# dsp_power.net
KiCad netlist of a schematic drawn in Altium Designer
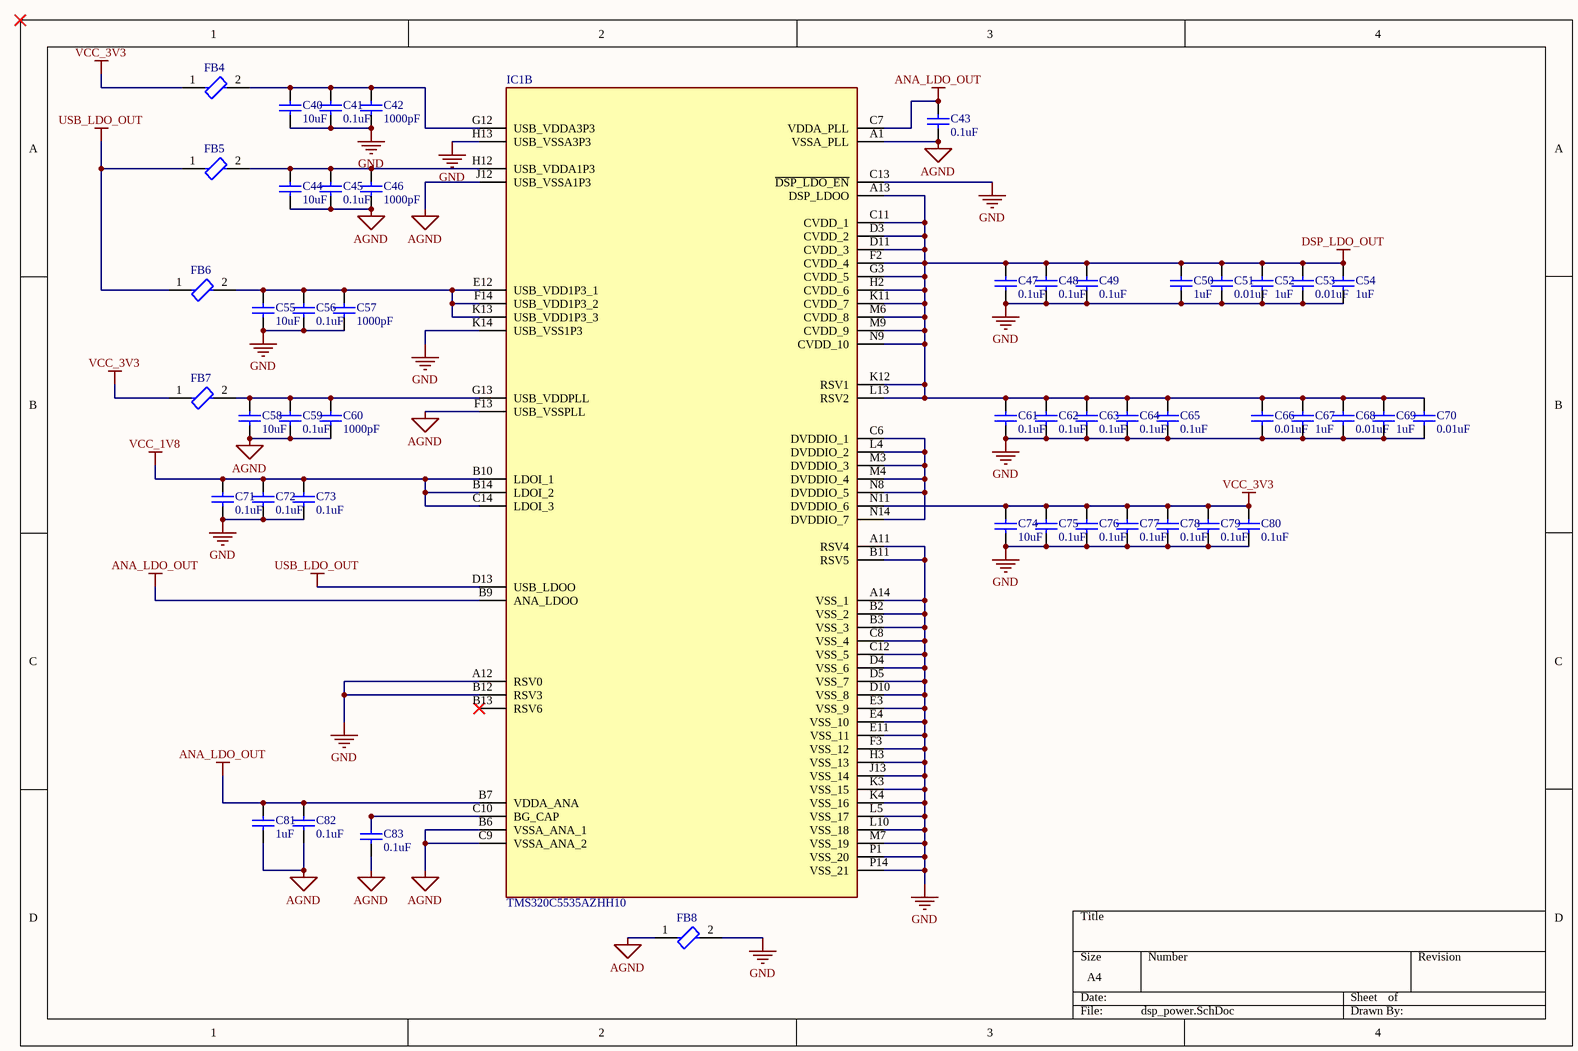
[diagram p0: dsp_power.SchDoc]

(export (version "E")
  (design (tool "Eeschema 10.0.6"))
  (components
    (comp (ref "C40")
      (value "10uF")
      (footprint "0805_C_S")
      (description "Capacitor")
      (fields (field (name "PUBLISHER") "Altium Limited"))
      (libsource (lib "Miscellaneous Devices") (part "Cap"))
    )
    (comp (ref "C41")
      (value "0.1uF")
      (footprint "0805_C_S")
      (description "Capacitor")
      (fields (field (name "PUBLISHER") "Altium Limited"))
      (libsource (lib "Miscellaneous Devices") (part "Cap"))
    )
    (comp (ref "C42")
      (value "1000pF")
      (footprint "0805_C_S")
      (description "Capacitor")
      (fields (field (name "PUBLISHER") "Altium Limited"))
      (libsource (lib "Miscellaneous Devices") (part "Cap"))
    )
    (comp (ref "C43")
      (value "0.1uF")
      (footprint "0805_C_S")
      (description "Capacitor")
      (fields (field (name "PUBLISHER") "Altium Limited"))
      (libsource (lib "Miscellaneous Devices") (part "Cap"))
    )
    (comp (ref "C44")
      (value "10uF")
      (footprint "0805_C_S")
      (description "Capacitor")
      (fields (field (name "PUBLISHER") "Altium Limited"))
      (libsource (lib "Miscellaneous Devices") (part "Cap"))
    )
    (comp (ref "C45")
      (value "0.1uF")
      (footprint "0805_C_S")
      (description "Capacitor")
      (fields (field (name "PUBLISHER") "Altium Limited"))
      (libsource (lib "Miscellaneous Devices") (part "Cap"))
    )
    (comp (ref "C46")
      (value "1000pF")
      (footprint "0805_C_S")
      (description "Capacitor")
      (fields (field (name "PUBLISHER") "Altium Limited"))
      (libsource (lib "Miscellaneous Devices") (part "Cap"))
    )
    (comp (ref "C47")
      (value "0.1uF")
      (footprint "0805_C_S")
      (description "Capacitor")
      (fields (field (name "PUBLISHER") "Altium Limited"))
      (libsource (lib "Miscellaneous Devices") (part "Cap"))
    )
    (comp (ref "C48")
      (value "0.1uF")
      (footprint "0805_C_S")
      (description "Capacitor")
      (fields (field (name "PUBLISHER") "Altium Limited"))
      (libsource (lib "Miscellaneous Devices") (part "Cap"))
    )
    (comp (ref "C49")
      (value "0.1uF")
      (footprint "0805_C_S")
      (description "Capacitor")
      (fields (field (name "PUBLISHER") "Altium Limited"))
      (libsource (lib "Miscellaneous Devices") (part "Cap"))
    )
    (comp (ref "C50")
      (value "1uF")
      (footprint "0805_C_S")
      (description "Capacitor")
      (fields (field (name "PUBLISHER") "Altium Limited"))
      (libsource (lib "Miscellaneous Devices") (part "Cap"))
    )
    (comp (ref "C51")
      (value "0.01uF")
      (footprint "0805_C_S")
      (description "Capacitor")
      (fields (field (name "PUBLISHER") "Altium Limited"))
      (libsource (lib "Miscellaneous Devices") (part "Cap"))
    )
    (comp (ref "C52")
      (value "1uF")
      (footprint "0805_C_S")
      (description "Capacitor")
      (fields (field (name "PUBLISHER") "Altium Limited"))
      (libsource (lib "Miscellaneous Devices") (part "Cap"))
    )
    (comp (ref "C53")
      (value "0.01uF")
      (footprint "0805_C_S")
      (description "Capacitor")
      (fields (field (name "PUBLISHER") "Altium Limited"))
      (libsource (lib "Miscellaneous Devices") (part "Cap"))
    )
    (comp (ref "C54")
      (value "1uF")
      (footprint "0805_C_S")
      (description "Capacitor")
      (fields (field (name "PUBLISHER") "Altium Limited"))
      (libsource (lib "Miscellaneous Devices") (part "Cap"))
    )
    (comp (ref "C55")
      (value "10uF")
      (footprint "0805_C_S")
      (description "Capacitor")
      (fields (field (name "PUBLISHER") "Altium Limited"))
      (libsource (lib "Miscellaneous Devices") (part "Cap"))
    )
    (comp (ref "C56")
      (value "0.1uF")
      (footprint "0805_C_S")
      (description "Capacitor")
      (fields (field (name "PUBLISHER") "Altium Limited"))
      (libsource (lib "Miscellaneous Devices") (part "Cap"))
    )
    (comp (ref "C57")
      (value "1000pF")
      (footprint "0805_C_S")
      (description "Capacitor")
      (fields (field (name "PUBLISHER") "Altium Limited"))
      (libsource (lib "Miscellaneous Devices") (part "Cap"))
    )
    (comp (ref "C58")
      (value "10uF")
      (footprint "0805_C_S")
      (description "Capacitor")
      (fields (field (name "PUBLISHER") "Altium Limited"))
      (libsource (lib "Miscellaneous Devices") (part "Cap"))
    )
    (comp (ref "C59")
      (value "0.1uF")
      (footprint "0805_C_S")
      (description "Capacitor")
      (fields (field (name "PUBLISHER") "Altium Limited"))
      (libsource (lib "Miscellaneous Devices") (part "Cap"))
    )
    (comp (ref "C60")
      (value "1000pF")
      (footprint "0805_C_S")
      (description "Capacitor")
      (fields (field (name "PUBLISHER") "Altium Limited"))
      (libsource (lib "Miscellaneous Devices") (part "Cap"))
    )
    (comp (ref "C61")
      (value "0.1uF")
      (footprint "0805_C_S")
      (description "Capacitor")
      (fields (field (name "PUBLISHER") "Altium Limited"))
      (libsource (lib "Miscellaneous Devices") (part "Cap"))
    )
    (comp (ref "C62")
      (value "0.1uF")
      (footprint "0805_C_S")
      (description "Capacitor")
      (fields (field (name "PUBLISHER") "Altium Limited"))
      (libsource (lib "Miscellaneous Devices") (part "Cap"))
    )
    (comp (ref "C63")
      (value "0.1uF")
      (footprint "0805_C_S")
      (description "Capacitor")
      (fields (field (name "PUBLISHER") "Altium Limited"))
      (libsource (lib "Miscellaneous Devices") (part "Cap"))
    )
    (comp (ref "C64")
      (value "0.1uF")
      (footprint "0805_C_S")
      (description "Capacitor")
      (fields (field (name "PUBLISHER") "Altium Limited"))
      (libsource (lib "Miscellaneous Devices") (part "Cap"))
    )
    (comp (ref "C65")
      (value "0.1uF")
      (footprint "0805_C_S")
      (description "Capacitor")
      (fields (field (name "PUBLISHER") "Altium Limited"))
      (libsource (lib "Miscellaneous Devices") (part "Cap"))
    )
    (comp (ref "C66")
      (value "0.01uF")
      (footprint "0805_C_S")
      (description "Capacitor")
      (fields (field (name "PUBLISHER") "Altium Limited"))
      (libsource (lib "Miscellaneous Devices") (part "Cap"))
    )
    (comp (ref "C67")
      (value "1uF")
      (footprint "0805_C_S")
      (description "Capacitor")
      (fields (field (name "PUBLISHER") "Altium Limited"))
      (libsource (lib "Miscellaneous Devices") (part "Cap"))
    )
    (comp (ref "C68")
      (value "0.01uF")
      (footprint "0805_C_S")
      (description "Capacitor")
      (fields (field (name "PUBLISHER") "Altium Limited"))
      (libsource (lib "Miscellaneous Devices") (part "Cap"))
    )
    (comp (ref "C69")
      (value "1uF")
      (footprint "0805_C_S")
      (description "Capacitor")
      (fields (field (name "PUBLISHER") "Altium Limited"))
      (libsource (lib "Miscellaneous Devices") (part "Cap"))
    )
    (comp (ref "C70")
      (value "0.01uF")
      (footprint "0805_C_S")
      (description "Capacitor")
      (fields (field (name "PUBLISHER") "Altium Limited"))
      (libsource (lib "Miscellaneous Devices") (part "Cap"))
    )
    (comp (ref "C71")
      (value "0.1uF")
      (footprint "0805_C_S")
      (description "Capacitor")
      (fields (field (name "PUBLISHER") "Altium Limited"))
      (libsource (lib "Miscellaneous Devices") (part "Cap"))
    )
    (comp (ref "C72")
      (value "0.1uF")
      (footprint "0805_C_S")
      (description "Capacitor")
      (fields (field (name "PUBLISHER") "Altium Limited"))
      (libsource (lib "Miscellaneous Devices") (part "Cap"))
    )
    (comp (ref "C73")
      (value "0.1uF")
      (footprint "0805_C_S")
      (description "Capacitor")
      (fields (field (name "PUBLISHER") "Altium Limited"))
      (libsource (lib "Miscellaneous Devices") (part "Cap"))
    )
    (comp (ref "C74")
      (value "10uF")
      (footprint "0805_C_S")
      (description "Capacitor")
      (fields (field (name "PUBLISHER") "Altium Limited"))
      (libsource (lib "Miscellaneous Devices") (part "Cap"))
    )
    (comp (ref "C75")
      (value "0.1uF")
      (footprint "0805_C_S")
      (description "Capacitor")
      (fields (field (name "PUBLISHER") "Altium Limited"))
      (libsource (lib "Miscellaneous Devices") (part "Cap"))
    )
    (comp (ref "C76")
      (value "0.1uF")
      (footprint "0805_C_S")
      (description "Capacitor")
      (fields (field (name "PUBLISHER") "Altium Limited"))
      (libsource (lib "Miscellaneous Devices") (part "Cap"))
    )
    (comp (ref "C77")
      (value "0.1uF")
      (footprint "0805_C_S")
      (description "Capacitor")
      (fields (field (name "PUBLISHER") "Altium Limited"))
      (libsource (lib "Miscellaneous Devices") (part "Cap"))
    )
    (comp (ref "C78")
      (value "0.1uF")
      (footprint "0805_C_S")
      (description "Capacitor")
      (fields (field (name "PUBLISHER") "Altium Limited"))
      (libsource (lib "Miscellaneous Devices") (part "Cap"))
    )
    (comp (ref "C79")
      (value "0.1uF")
      (footprint "0805_C_S")
      (description "Capacitor")
      (fields (field (name "PUBLISHER") "Altium Limited"))
      (libsource (lib "Miscellaneous Devices") (part "Cap"))
    )
    (comp (ref "C80")
      (value "0.1uF")
      (footprint "0805_C_S")
      (description "Capacitor")
      (fields (field (name "PUBLISHER") "Altium Limited"))
      (libsource (lib "Miscellaneous Devices") (part "Cap"))
    )
    (comp (ref "C81")
      (value "1uF")
      (footprint "0805_C_S")
      (description "Capacitor")
      (fields (field (name "PUBLISHER") "Altium Limited"))
      (libsource (lib "Miscellaneous Devices") (part "Cap"))
    )
    (comp (ref "C82")
      (value "0.1uF")
      (footprint "0805_C_S")
      (description "Capacitor")
      (fields (field (name "PUBLISHER") "Altium Limited"))
      (libsource (lib "Miscellaneous Devices") (part "Cap"))
    )
    (comp (ref "C83")
      (value "0.1uF")
      (footprint "0805_C_S")
      (description "Capacitor")
      (fields (field (name "PUBLISHER") "Altium Limited"))
      (libsource (lib "Miscellaneous Devices") (part "Cap"))
    )
    (comp (ref "FB4")
      (value "BLM21AG151SN1D")
      (footprint "FP-BLM21-0_2-t0_85-e0_5-MFG")
      (description "Chip Ferrite Bead, 0805, 150Ω @ 100MHz, 0.09Ω, 25%, 1A")
      (fields (field (name "TOLERANCE") "25%"))
      (libsource (lib "Altium Content Vault") (part "5f30dd21d616792df468990f7003faa"))
    )
    (comp (ref "FB5")
      (value "BLM21AG151SN1D")
      (footprint "FP-BLM21-0_2-t0_85-e0_5-MFG")
      (description "Chip Ferrite Bead, 0805, 150Ω @ 100MHz, 0.09Ω, 25%, 1A")
      (fields (field (name "TOLERANCE") "25%"))
      (libsource (lib "Altium Content Vault") (part "5f30dd21d616792df468990f7003faa"))
    )
    (comp (ref "FB6")
      (value "BLM21AG151SN1D")
      (footprint "FP-BLM21-0_2-t0_85-e0_5-MFG")
      (description "Chip Ferrite Bead, 0805, 150Ω @ 100MHz, 0.09Ω, 25%, 1A")
      (fields (field (name "TOLERANCE") "25%"))
      (libsource (lib "Altium Content Vault") (part "5f30dd21d616792df468990f7003faa"))
    )
    (comp (ref "FB7")
      (value "BLM21AG151SN1D")
      (footprint "FP-BLM21-0_2-t0_85-e0_5-MFG")
      (description "Chip Ferrite Bead, 0805, 150Ω @ 100MHz, 0.09Ω, 25%, 1A")
      (fields (field (name "TOLERANCE") "25%"))
      (libsource (lib "Altium Content Vault") (part "5f30dd21d616792df468990f7003faa"))
    )
    (comp (ref "FB8")
      (value "BLM21AG151SN1D")
      (footprint "FP-BLM21-0_2-t0_85-e0_5-MFG")
      (description "Chip Ferrite Bead, 0805, 150Ω @ 100MHz, 0.09Ω, 25%, 1A")
      (fields (field (name "TOLERANCE") "25%"))
      (libsource (lib "Altium Content Vault") (part "5f30dd21d616792df468990f7003faa"))
    )
    (comp (ref "IC1")
      (value "TMS320C5535AZHH10")
      (footprint "SamacSys:BGA144C80P14X14_1200X1200X140")
      (description "Integrated Circuit")
      (fields (field (name "MOUSER PART NUMBER") "595-MS320C5535AZHH10"))
      (libsource (lib "Schlib1") (part "TMS320C5535AZHH10"))
    )
  )
  (nets
    (net (code "1") (name "AGND") (class "Default")
      (node (ref "C43") (pin "1") (pinfunction "1_1") (pintype "passive"))
      (node (ref "C44") (pin "1") (pinfunction "1_1") (pintype "passive"))
      (node (ref "C45") (pin "1") (pinfunction "1_1") (pintype "passive"))
      (node (ref "C46") (pin "1") (pinfunction "1_1") (pintype "passive"))
      (node (ref "C58") (pin "1") (pinfunction "1_1") (pintype "passive"))
      (node (ref "C59") (pin "1") (pinfunction "1_1") (pintype "passive"))
      (node (ref "C60") (pin "1") (pinfunction "1_1") (pintype "passive"))
      (node (ref "C81") (pin "1") (pinfunction "1_1") (pintype "passive"))
      (node (ref "C82") (pin "1") (pinfunction "1_1") (pintype "passive"))
      (node (ref "C83") (pin "1") (pinfunction "1_1") (pintype "passive"))
      (node (ref "FB8") (pin "1") (pinfunction "1_1") (pintype "passive"))
      (node (ref "IC1") (pin "A1") (pinfunction "VSSA_PLL_A1") (pintype "passive"))
      (node (ref "IC1") (pin "B6") (pinfunction "VSSA_ANA_1_B6") (pintype "passive"))
      (node (ref "IC1") (pin "C9") (pinfunction "VSSA_ANA_2_C9") (pintype "passive"))
      (node (ref "IC1") (pin "F13") (pinfunction "USB_VSSPLL_F13") (pintype "passive"))
      (node (ref "IC1") (pin "J12") (pinfunction "USB_VSSA1P3_J12") (pintype "passive"))
    )
    (net (code "2") (name "ANA_LDO_OUT") (class "Default")
      (node (ref "C43") (pin "2") (pinfunction "2_2") (pintype "passive"))
      (node (ref "C81") (pin "2") (pinfunction "2_2") (pintype "passive"))
      (node (ref "C82") (pin "2") (pinfunction "2_2") (pintype "passive"))
      (node (ref "IC1") (pin "B7") (pinfunction "VDDA_ANA_B7") (pintype "passive"))
      (node (ref "IC1") (pin "B9") (pinfunction "ANA_LDOO_B9") (pintype "passive"))
      (node (ref "IC1") (pin "C7") (pinfunction "VDDA_PLL_C7") (pintype "passive"))
    )
    (net (code "3") (name "DSP_LDO_OUT") (class "Default")
      (node (ref "C47") (pin "2") (pinfunction "2_2") (pintype "passive"))
      (node (ref "C48") (pin "2") (pinfunction "2_2") (pintype "passive"))
      (node (ref "C49") (pin "2") (pinfunction "2_2") (pintype "passive"))
      (node (ref "C50") (pin "2") (pinfunction "2_2") (pintype "passive"))
      (node (ref "C51") (pin "2") (pinfunction "2_2") (pintype "passive"))
      (node (ref "C52") (pin "2") (pinfunction "2_2") (pintype "passive"))
      (node (ref "C53") (pin "2") (pinfunction "2_2") (pintype "passive"))
      (node (ref "C54") (pin "2") (pinfunction "2_2") (pintype "passive"))
      (node (ref "C61") (pin "2") (pinfunction "2_2") (pintype "passive"))
      (node (ref "C62") (pin "2") (pinfunction "2_2") (pintype "passive"))
      (node (ref "C63") (pin "2") (pinfunction "2_2") (pintype "passive"))
      (node (ref "C64") (pin "2") (pinfunction "2_2") (pintype "passive"))
      (node (ref "C65") (pin "2") (pinfunction "2_2") (pintype "passive"))
      (node (ref "C66") (pin "2") (pinfunction "2_2") (pintype "passive"))
      (node (ref "C67") (pin "2") (pinfunction "2_2") (pintype "passive"))
      (node (ref "C68") (pin "2") (pinfunction "2_2") (pintype "passive"))
      (node (ref "C69") (pin "2") (pinfunction "2_2") (pintype "passive"))
      (node (ref "C70") (pin "2") (pinfunction "2_2") (pintype "passive"))
      (node (ref "IC1") (pin "A13") (pinfunction "DSP_LDOO_A13") (pintype "passive"))
      (node (ref "IC1") (pin "C11") (pinfunction "CVDD_1_C11") (pintype "passive"))
      (node (ref "IC1") (pin "D11") (pinfunction "CVDD_3_D11") (pintype "passive"))
      (node (ref "IC1") (pin "D3") (pinfunction "CVDD_2_D3") (pintype "passive"))
      (node (ref "IC1") (pin "F2") (pinfunction "CVDD_4_F2") (pintype "passive"))
      (node (ref "IC1") (pin "G3") (pinfunction "CVDD_5_G3") (pintype "passive"))
      (node (ref "IC1") (pin "H2") (pinfunction "CVDD_6_H2") (pintype "passive"))
      (node (ref "IC1") (pin "K11") (pinfunction "CVDD_7_K11") (pintype "passive"))
      (node (ref "IC1") (pin "K12") (pinfunction "RSV1_K12") (pintype "passive"))
      (node (ref "IC1") (pin "L13") (pinfunction "RSV2_L13") (pintype "passive"))
      (node (ref "IC1") (pin "M6") (pinfunction "CVDD_8_M6") (pintype "passive"))
      (node (ref "IC1") (pin "M9") (pinfunction "CVDD_9_M9") (pintype "passive"))
      (node (ref "IC1") (pin "N9") (pinfunction "CVDD_10_N9") (pintype "passive"))
    )
    (net (code "4") (name "GND") (class "Default")
      (node (ref "C40") (pin "1") (pinfunction "1_1") (pintype "passive"))
      (node (ref "C41") (pin "1") (pinfunction "1_1") (pintype "passive"))
      (node (ref "C42") (pin "1") (pinfunction "1_1") (pintype "passive"))
      (node (ref "C47") (pin "1") (pinfunction "1_1") (pintype "passive"))
      (node (ref "C48") (pin "1") (pinfunction "1_1") (pintype "passive"))
      (node (ref "C49") (pin "1") (pinfunction "1_1") (pintype "passive"))
      (node (ref "C50") (pin "1") (pinfunction "1_1") (pintype "passive"))
      (node (ref "C51") (pin "1") (pinfunction "1_1") (pintype "passive"))
      (node (ref "C52") (pin "1") (pinfunction "1_1") (pintype "passive"))
      (node (ref "C53") (pin "1") (pinfunction "1_1") (pintype "passive"))
      (node (ref "C54") (pin "1") (pinfunction "1_1") (pintype "passive"))
      (node (ref "C55") (pin "1") (pinfunction "1_1") (pintype "passive"))
      (node (ref "C56") (pin "1") (pinfunction "1_1") (pintype "passive"))
      (node (ref "C57") (pin "1") (pinfunction "1_1") (pintype "passive"))
      (node (ref "C61") (pin "1") (pinfunction "1_1") (pintype "passive"))
      (node (ref "C62") (pin "1") (pinfunction "1_1") (pintype "passive"))
      (node (ref "C63") (pin "1") (pinfunction "1_1") (pintype "passive"))
      (node (ref "C64") (pin "1") (pinfunction "1_1") (pintype "passive"))
      (node (ref "C65") (pin "1") (pinfunction "1_1") (pintype "passive"))
      (node (ref "C66") (pin "1") (pinfunction "1_1") (pintype "passive"))
      (node (ref "C67") (pin "1") (pinfunction "1_1") (pintype "passive"))
      (node (ref "C68") (pin "1") (pinfunction "1_1") (pintype "passive"))
      (node (ref "C69") (pin "1") (pinfunction "1_1") (pintype "passive"))
      (node (ref "C70") (pin "1") (pinfunction "1_1") (pintype "passive"))
      (node (ref "C71") (pin "1") (pinfunction "1_1") (pintype "passive"))
      (node (ref "C72") (pin "1") (pinfunction "1_1") (pintype "passive"))
      (node (ref "C73") (pin "1") (pinfunction "1_1") (pintype "passive"))
      (node (ref "C74") (pin "1") (pinfunction "1_1") (pintype "passive"))
      (node (ref "C75") (pin "1") (pinfunction "1_1") (pintype "passive"))
      (node (ref "C76") (pin "1") (pinfunction "1_1") (pintype "passive"))
      (node (ref "C77") (pin "1") (pinfunction "1_1") (pintype "passive"))
      (node (ref "C78") (pin "1") (pinfunction "1_1") (pintype "passive"))
      (node (ref "C79") (pin "1") (pinfunction "1_1") (pintype "passive"))
      (node (ref "C80") (pin "1") (pinfunction "1_1") (pintype "passive"))
      (node (ref "FB8") (pin "2") (pinfunction "2_2") (pintype "passive"))
      (node (ref "IC1") (pin "A11") (pinfunction "RSV4_A11") (pintype "passive"))
      (node (ref "IC1") (pin "A12") (pinfunction "RSV0_A12") (pintype "passive"))
      (node (ref "IC1") (pin "A14") (pinfunction "VSS_1_A14") (pintype "passive"))
      (node (ref "IC1") (pin "B11") (pinfunction "RSV5_B11") (pintype "passive"))
      (node (ref "IC1") (pin "B12") (pinfunction "RSV3_B12") (pintype "passive"))
      (node (ref "IC1") (pin "B2") (pinfunction "VSS_2_B2") (pintype "passive"))
      (node (ref "IC1") (pin "B3") (pinfunction "VSS_3_B3") (pintype "passive"))
      (node (ref "IC1") (pin "C12") (pinfunction "VSS_5_C12") (pintype "passive"))
      (node (ref "IC1") (pin "C13") (pinfunction "~{DSP_LDO_EN}_C13") (pintype "passive"))
      (node (ref "IC1") (pin "C8") (pinfunction "VSS_4_C8") (pintype "passive"))
      (node (ref "IC1") (pin "D10") (pinfunction "VSS_8_D10") (pintype "passive"))
      (node (ref "IC1") (pin "D4") (pinfunction "VSS_6_D4") (pintype "passive"))
      (node (ref "IC1") (pin "D5") (pinfunction "VSS_7_D5") (pintype "passive"))
      (node (ref "IC1") (pin "E11") (pinfunction "VSS_11_E11") (pintype "passive"))
      (node (ref "IC1") (pin "E3") (pinfunction "VSS_9_E3") (pintype "passive"))
      (node (ref "IC1") (pin "E4") (pinfunction "VSS_10_E4") (pintype "passive"))
      (node (ref "IC1") (pin "F3") (pinfunction "VSS_12_F3") (pintype "passive"))
      (node (ref "IC1") (pin "H13") (pinfunction "USB_VSSA3P3_H13") (pintype "passive"))
      (node (ref "IC1") (pin "H3") (pinfunction "VSS_13_H3") (pintype "passive"))
      (node (ref "IC1") (pin "J13") (pinfunction "VSS_14_J13") (pintype "passive"))
      (node (ref "IC1") (pin "K14") (pinfunction "USB_VSS1P3_K14") (pintype "passive"))
      (node (ref "IC1") (pin "K3") (pinfunction "VSS_15_K3") (pintype "passive"))
      (node (ref "IC1") (pin "K4") (pinfunction "VSS_16_K4") (pintype "passive"))
      (node (ref "IC1") (pin "L10") (pinfunction "VSS_18_L10") (pintype "passive"))
      (node (ref "IC1") (pin "L5") (pinfunction "VSS_17_L5") (pintype "passive"))
      (node (ref "IC1") (pin "M7") (pinfunction "VSS_19_M7") (pintype "passive"))
      (node (ref "IC1") (pin "P1") (pinfunction "VSS_20_P1") (pintype "passive"))
      (node (ref "IC1") (pin "P14") (pinfunction "VSS_21_P14") (pintype "passive"))
    )
    (net (code "5") (name "Net-(IC1B-BG_CAP)") (class "Default")
      (node (ref "C83") (pin "2") (pinfunction "2_2") (pintype "passive"))
      (node (ref "IC1") (pin "C10") (pinfunction "BG_CAP_C10") (pintype "passive"))
    )
    (net (code "6") (name "Net-(IC1B-DVDDIO_1)") (class "Default")
      (node (ref "IC1") (pin "C6") (pinfunction "DVDDIO_1_C6") (pintype "passive"))
      (node (ref "IC1") (pin "L4") (pinfunction "DVDDIO_2_L4") (pintype "passive"))
      (node (ref "IC1") (pin "M3") (pinfunction "DVDDIO_3_M3") (pintype "passive"))
      (node (ref "IC1") (pin "M4") (pinfunction "DVDDIO_4_M4") (pintype "passive"))
      (node (ref "IC1") (pin "N14") (pinfunction "DVDDIO_7_N14") (pintype "passive"))
      (node (ref "IC1") (pin "N8") (pinfunction "DVDDIO_5_N8") (pintype "passive"))
    )
    (net (code "7") (name "Net-(IC1B-USB_VDD1P3_1)") (class "Default")
      (node (ref "C55") (pin "2") (pinfunction "2_2") (pintype "passive"))
      (node (ref "C56") (pin "2") (pinfunction "2_2") (pintype "passive"))
      (node (ref "C57") (pin "2") (pinfunction "2_2") (pintype "passive"))
      (node (ref "FB6") (pin "2") (pinfunction "2_2") (pintype "passive"))
      (node (ref "IC1") (pin "E12") (pinfunction "USB_VDD1P3_1_E12") (pintype "passive"))
      (node (ref "IC1") (pin "F14") (pinfunction "USB_VDD1P3_2_F14") (pintype "passive"))
      (node (ref "IC1") (pin "K13") (pinfunction "USB_VDD1P3_3_K13") (pintype "passive"))
    )
    (net (code "8") (name "Net-(IC1B-USB_VDDA1P3)") (class "Default")
      (node (ref "C44") (pin "2") (pinfunction "2_2") (pintype "passive"))
      (node (ref "C45") (pin "2") (pinfunction "2_2") (pintype "passive"))
      (node (ref "C46") (pin "2") (pinfunction "2_2") (pintype "passive"))
      (node (ref "FB5") (pin "2") (pinfunction "2_2") (pintype "passive"))
      (node (ref "IC1") (pin "H12") (pinfunction "USB_VDDA1P3_H12") (pintype "passive"))
    )
    (net (code "9") (name "Net-(IC1B-USB_VDDA3P3)") (class "Default")
      (node (ref "C40") (pin "2") (pinfunction "2_2") (pintype "passive"))
      (node (ref "C41") (pin "2") (pinfunction "2_2") (pintype "passive"))
      (node (ref "C42") (pin "2") (pinfunction "2_2") (pintype "passive"))
      (node (ref "FB4") (pin "2") (pinfunction "2_2") (pintype "passive"))
      (node (ref "IC1") (pin "G12") (pinfunction "USB_VDDA3P3_G12") (pintype "passive"))
    )
    (net (code "10") (name "Net-(IC1B-USB_VDDPLL)") (class "Default")
      (node (ref "C58") (pin "2") (pinfunction "2_2") (pintype "passive"))
      (node (ref "C59") (pin "2") (pinfunction "2_2") (pintype "passive"))
      (node (ref "C60") (pin "2") (pinfunction "2_2") (pintype "passive"))
      (node (ref "FB7") (pin "2") (pinfunction "2_2") (pintype "passive"))
      (node (ref "IC1") (pin "G13") (pinfunction "USB_VDDPLL_G13") (pintype "passive"))
    )
    (net (code "11") (name "USB_LDO_OUT") (class "Default")
      (node (ref "FB5") (pin "1") (pinfunction "1_1") (pintype "passive"))
      (node (ref "FB6") (pin "1") (pinfunction "1_1") (pintype "passive"))
      (node (ref "IC1") (pin "D13") (pinfunction "USB_LDOO_D13") (pintype "passive"))
    )
    (net (code "12") (name "VCC_1V8") (class "Default")
      (node (ref "C71") (pin "2") (pinfunction "2_2") (pintype "passive"))
      (node (ref "C72") (pin "2") (pinfunction "2_2") (pintype "passive"))
      (node (ref "C73") (pin "2") (pinfunction "2_2") (pintype "passive"))
      (node (ref "IC1") (pin "B10") (pinfunction "LDOI_1_B10") (pintype "passive"))
      (node (ref "IC1") (pin "B14") (pinfunction "LDOI_2_B14") (pintype "passive"))
      (node (ref "IC1") (pin "C14") (pinfunction "LDOI_3_C14") (pintype "passive"))
    )
    (net (code "13") (name "VCC_3V3") (class "Default")
      (node (ref "C74") (pin "2") (pinfunction "2_2") (pintype "passive"))
      (node (ref "C75") (pin "2") (pinfunction "2_2") (pintype "passive"))
      (node (ref "C76") (pin "2") (pinfunction "2_2") (pintype "passive"))
      (node (ref "C77") (pin "2") (pinfunction "2_2") (pintype "passive"))
      (node (ref "C78") (pin "2") (pinfunction "2_2") (pintype "passive"))
      (node (ref "C79") (pin "2") (pinfunction "2_2") (pintype "passive"))
      (node (ref "C80") (pin "2") (pinfunction "2_2") (pintype "passive"))
      (node (ref "FB4") (pin "1") (pinfunction "1_1") (pintype "passive"))
      (node (ref "FB7") (pin "1") (pinfunction "1_1") (pintype "passive"))
      (node (ref "IC1") (pin "N11") (pinfunction "DVDDIO_6_N11") (pintype "passive"))
    )
    (net (code "14") (name "unconnected-(IC1B-RSV6-PadB13)") (class "Default")
      (node (ref "IC1") (pin "B13") (pinfunction "RSV6_B13") (pintype "passive+no_connect"))
    )
  )
)
